# Hub.net
KiCad netlist of a schematic drawn in EAGLE
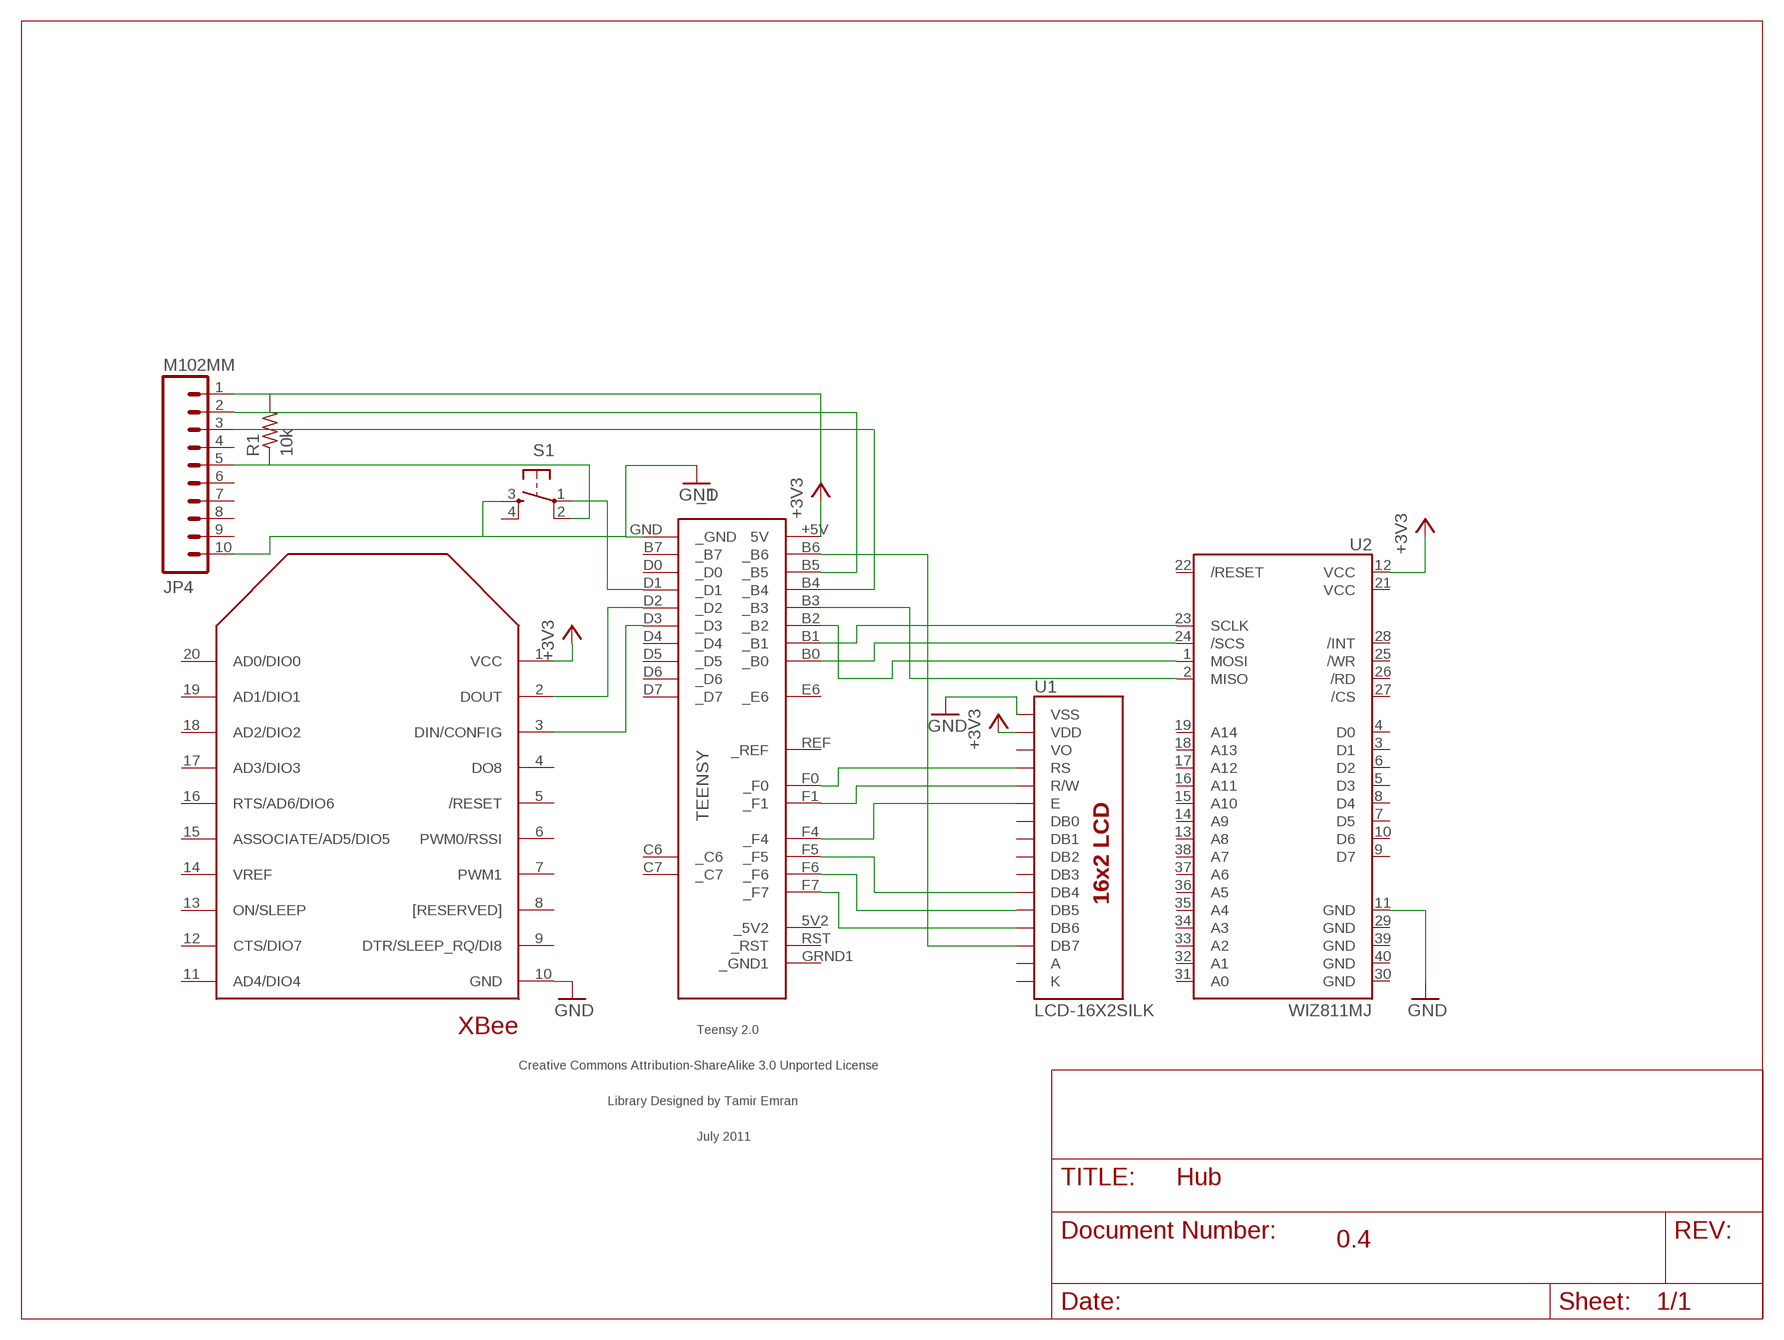
[diagram p0: schematic, sheet 1]

(export (version "E")
  (design (tool "Eeschema 10.0.6"))
  (components
    (comp (ref "JP4")
      (value "M102MM")
      (footprint "eagle-import:1X10-2MM")
      (libsource (lib "eagle-import") (part "M102MM"))
    )
    (comp (ref "R1")
      (value "10k")
      (footprint "eagle-import:0207_7")
      (libsource (lib "eagle-import") (part "R-US_0207/7"))
    )
    (comp (ref "S1")
      (value "TAC_SWITCHPTH")
      (footprint "eagle-import:TACTILE-PTH")
      (libsource (lib "eagle-import") (part "TAC_SWITCHPTH"))
    )
    (comp (ref "U$1")
      (value "XBEE")
      (footprint "eagle-import:XBEE")
      (libsource (lib "eagle-import") (part "XBEE"))
    )
    (comp (ref "U1")
      (value "LCD-16X2SILK")
      (footprint "eagle-import:LCD-16X2")
      (libsource (lib "eagle-import") (part "LCD-16X2SILK"))
    )
    (comp (ref "U2")
      (value "WIZ811MJ")
      (footprint "eagle-import:WIZ811MJ")
      (libsource (lib "eagle-import") (part "WIZ811MJ"))
    )
    (comp (ref "_1")
      (value "TEENSY")
      (footprint "eagle-import:TEENSY")
      (libsource (lib "eagle-import") (part "TEENSY"))
    )
  )
  (nets
    (net (code "1") (name "+3V3") (class "Default")
      (node (ref "U$1") (pin "1") (pinfunction "VCC_1") (pintype "bidirectional"))
      (node (ref "U1") (pin "2") (pinfunction "VDD_2") (pintype "power_in"))
      (node (ref "U2") (pin "12") (pinfunction "VCC_12") (pintype "bidirectional"))
      (node (ref "_1") (pin "+5V") (pinfunction "5V_+5V") (pintype "bidirectional"))
    )
    (net (code "2") (name "/A") (class "Default")
      (node (ref "U1") (pin "15") (pinfunction "A_15") (pintype "power_in"))
    )
    (net (code "3") (name "/K") (class "Default")
      (node (ref "U1") (pin "16") (pinfunction "K_16") (pintype "power_in"))
    )
    (net (code "4") (name "GND") (class "Default")
      (node (ref "JP4") (pin "10") (pinfunction "10_10") (pintype "passive"))
      (node (ref "S1") (pin "3") (pinfunction "3_3") (pintype "passive"))
      (node (ref "U$1") (pin "10") (pinfunction "GND_10") (pintype "bidirectional"))
      (node (ref "U1") (pin "1") (pinfunction "VSS_1") (pintype "power_in"))
      (node (ref "U2") (pin "11") (pinfunction "GND_11") (pintype "bidirectional"))
      (node (ref "_1") (pin "GND") (pinfunction "_GND_GND") (pintype "bidirectional"))
    )
    (net (code "5") (name "Net-(JP4-Pad1)") (class "Default")
      (node (ref "JP4") (pin "1") (pinfunction "1_1") (pintype "passive"))
      (node (ref "R1") (pin "2") (pinfunction "2_2") (pintype "passive"))
    )
    (net (code "6") (name "Net-(JP4-Pad5)") (class "Default")
      (node (ref "JP4") (pin "5") (pinfunction "5_5") (pintype "passive"))
      (node (ref "R1") (pin "1") (pinfunction "1_1") (pintype "passive"))
      (node (ref "S1") (pin "2") (pinfunction "2_2") (pintype "passive"))
    )
    (net (code "7") (name "Net-(U$1-DIN{slash}CONFIG)") (class "Default")
      (node (ref "U$1") (pin "3") (pinfunction "DIN/CONFIG_3") (pintype "bidirectional"))
      (node (ref "_1") (pin "D3") (pinfunction "_D3_D3") (pintype "bidirectional"))
    )
    (net (code "8") (name "Net-(U$1-DOUT)") (class "Default")
      (node (ref "U$1") (pin "2") (pinfunction "DOUT_2") (pintype "bidirectional"))
      (node (ref "_1") (pin "D2") (pinfunction "_D2_D2") (pintype "bidirectional"))
    )
    (net (code "9") (name "Net-(U1-DB4)") (class "Default")
      (node (ref "U1") (pin "11") (pinfunction "DB4_11") (pintype "bidirectional"))
      (node (ref "_1") (pin "F5") (pinfunction "_F5_F5") (pintype "bidirectional"))
    )
    (net (code "10") (name "Net-(U1-DB5)") (class "Default")
      (node (ref "U1") (pin "12") (pinfunction "DB5_12") (pintype "bidirectional"))
      (node (ref "_1") (pin "F6") (pinfunction "_F6_F6") (pintype "bidirectional"))
    )
    (net (code "11") (name "Net-(U1-DB6)") (class "Default")
      (node (ref "U1") (pin "13") (pinfunction "DB6_13") (pintype "bidirectional"))
      (node (ref "_1") (pin "F7") (pinfunction "_F7_F7") (pintype "bidirectional"))
    )
    (net (code "12") (name "Net-(U1-DB7)") (class "Default")
      (node (ref "U1") (pin "14") (pinfunction "DB7_14") (pintype "bidirectional"))
      (node (ref "_1") (pin "B6") (pinfunction "_B6_B6") (pintype "bidirectional"))
    )
    (net (code "13") (name "Net-(U1-E)") (class "Default")
      (node (ref "U1") (pin "6") (pinfunction "E_6") (pintype "input"))
      (node (ref "_1") (pin "F4") (pinfunction "_F4_F4") (pintype "bidirectional"))
    )
    (net (code "14") (name "Net-(U1-RS)") (class "Default")
      (node (ref "U1") (pin "4") (pinfunction "RS_4") (pintype "input"))
      (node (ref "_1") (pin "F0") (pinfunction "_F0_F0") (pintype "bidirectional"))
    )
    (net (code "15") (name "Net-(U1-R{slash}W)") (class "Default")
      (node (ref "U1") (pin "5") (pinfunction "R/W_5") (pintype "input"))
      (node (ref "_1") (pin "F1") (pinfunction "_F1_F1") (pintype "bidirectional"))
    )
    (net (code "16") (name "Net-(U2-MISO)") (class "Default")
      (node (ref "U2") (pin "2") (pinfunction "MISO_2") (pintype "bidirectional"))
      (node (ref "_1") (pin "B3") (pinfunction "_B3_B3") (pintype "bidirectional"))
    )
    (net (code "17") (name "Net-(U2-MOSI)") (class "Default")
      (node (ref "U2") (pin "1") (pinfunction "MOSI_1") (pintype "bidirectional"))
      (node (ref "_1") (pin "B2") (pinfunction "_B2_B2") (pintype "bidirectional"))
    )
    (net (code "18") (name "Net-(U2-SCLK)") (class "Default")
      (node (ref "U2") (pin "23") (pinfunction "SCLK_23") (pintype "bidirectional"))
      (node (ref "_1") (pin "B1") (pinfunction "_B1_B1") (pintype "bidirectional"))
    )
    (net (code "19") (name "Net-(U2-{slash}SCS)") (class "Default")
      (node (ref "U2") (pin "24") (pinfunction "/SCS_24") (pintype "bidirectional"))
      (node (ref "_1") (pin "B0") (pinfunction "_B0_B0") (pintype "bidirectional"))
    )
    (net (code "20") (name "Net-(_1-_B4)") (class "Default")
      (node (ref "JP4") (pin "3") (pinfunction "3_3") (pintype "passive"))
      (node (ref "_1") (pin "B4") (pinfunction "_B4_B4") (pintype "bidirectional"))
    )
    (net (code "21") (name "Net-(_1-_B5)") (class "Default")
      (node (ref "JP4") (pin "2") (pinfunction "2_2") (pintype "passive"))
      (node (ref "_1") (pin "B5") (pinfunction "_B5_B5") (pintype "bidirectional"))
    )
    (net (code "22") (name "Net-(_1-_D1)") (class "Default")
      (node (ref "S1") (pin "1") (pinfunction "1_1") (pintype "passive"))
      (node (ref "_1") (pin "D1") (pinfunction "_D1_D1") (pintype "bidirectional"))
    )
    (net (code "23") (name "unconnected-(JP4-Pad4)") (class "Default")
      (node (ref "JP4") (pin "4") (pinfunction "4_4") (pintype "passive"))
    )
    (net (code "24") (name "unconnected-(JP4-Pad6)") (class "Default")
      (node (ref "JP4") (pin "6") (pinfunction "6_6") (pintype "passive"))
    )
    (net (code "25") (name "unconnected-(JP4-Pad7)") (class "Default")
      (node (ref "JP4") (pin "7") (pinfunction "7_7") (pintype "passive"))
    )
    (net (code "26") (name "unconnected-(JP4-Pad8)") (class "Default")
      (node (ref "JP4") (pin "8") (pinfunction "8_8") (pintype "passive"))
    )
    (net (code "27") (name "unconnected-(JP4-Pad9)") (class "Default")
      (node (ref "JP4") (pin "9") (pinfunction "9_9") (pintype "passive"))
    )
    (net (code "28") (name "unconnected-(S1-Pad4)") (class "Default")
      (node (ref "S1") (pin "4") (pinfunction "4_4") (pintype "passive"))
    )
    (net (code "29") (name "unconnected-(U$1-AD0{slash}DIO0-Pad20)") (class "Default")
      (node (ref "U$1") (pin "20") (pinfunction "AD0/DIO0_20") (pintype "bidirectional"))
    )
    (net (code "30") (name "unconnected-(U$1-AD1{slash}DIO1-Pad19)") (class "Default")
      (node (ref "U$1") (pin "19") (pinfunction "AD1/DIO1_19") (pintype "bidirectional"))
    )
    (net (code "31") (name "unconnected-(U$1-AD2{slash}DIO2-Pad18)") (class "Default")
      (node (ref "U$1") (pin "18") (pinfunction "AD2/DIO2_18") (pintype "bidirectional"))
    )
    (net (code "32") (name "unconnected-(U$1-AD3{slash}DIO3-Pad17)") (class "Default")
      (node (ref "U$1") (pin "17") (pinfunction "AD3/DIO3_17") (pintype "bidirectional"))
    )
    (net (code "33") (name "unconnected-(U$1-AD4{slash}DIO4-Pad11)") (class "Default")
      (node (ref "U$1") (pin "11") (pinfunction "AD4/DIO4_11") (pintype "bidirectional"))
    )
    (net (code "34") (name "unconnected-(U$1-ASSOCIATE{slash}AD5{slash}DIO5-Pad15)") (class "Default")
      (node (ref "U$1") (pin "15") (pinfunction "ASSOCIATE/AD5/DIO5_15") (pintype "bidirectional"))
    )
    (net (code "35") (name "unconnected-(U$1-CTS{slash}DIO7-Pad12)") (class "Default")
      (node (ref "U$1") (pin "12") (pinfunction "CTS/DIO7_12") (pintype "bidirectional"))
    )
    (net (code "36") (name "unconnected-(U$1-DO8-Pad4)") (class "Default")
      (node (ref "U$1") (pin "4") (pinfunction "DO8_4") (pintype "bidirectional"))
    )
    (net (code "37") (name "unconnected-(U$1-DTR{slash}SLEEP_RQ{slash}DI8-Pad9)") (class "Default")
      (node (ref "U$1") (pin "9") (pinfunction "DTR/SLEEP_RQ/DI8_9") (pintype "bidirectional"))
    )
    (net (code "38") (name "unconnected-(U$1-ON{slash}SLEEP-Pad13)") (class "Default")
      (node (ref "U$1") (pin "13") (pinfunction "ON/SLEEP_13") (pintype "bidirectional"))
    )
    (net (code "39") (name "unconnected-(U$1-PWM0{slash}RSSI-Pad6)") (class "Default")
      (node (ref "U$1") (pin "6") (pinfunction "PWM0/RSSI_6") (pintype "bidirectional"))
    )
    (net (code "40") (name "unconnected-(U$1-PWM1-Pad7)") (class "Default")
      (node (ref "U$1") (pin "7") (pinfunction "PWM1_7") (pintype "bidirectional"))
    )
    (net (code "41") (name "unconnected-(U$1-RTS{slash}AD6{slash}DIO6-Pad16)") (class "Default")
      (node (ref "U$1") (pin "16") (pinfunction "RTS/AD6/DIO6_16") (pintype "bidirectional"))
    )
    (net (code "42") (name "unconnected-(U$1-VREF-Pad14)") (class "Default")
      (node (ref "U$1") (pin "14") (pinfunction "VREF_14") (pintype "bidirectional"))
    )
    (net (code "43") (name "unconnected-(U$1-[RESERVED]-Pad8)") (class "Default")
      (node (ref "U$1") (pin "8") (pinfunction "[RESERVED]_8") (pintype "bidirectional"))
    )
    (net (code "44") (name "unconnected-(U$1-{slash}RESET-Pad5)") (class "Default")
      (node (ref "U$1") (pin "5") (pinfunction "/RESET_5") (pintype "bidirectional"))
    )
    (net (code "45") (name "unconnected-(U1-DB0-Pad7)") (class "Default")
      (node (ref "U1") (pin "7") (pinfunction "DB0_7") (pintype "bidirectional"))
    )
    (net (code "46") (name "unconnected-(U1-DB1-Pad8)") (class "Default")
      (node (ref "U1") (pin "8") (pinfunction "DB1_8") (pintype "bidirectional"))
    )
    (net (code "47") (name "unconnected-(U1-DB2-Pad9)") (class "Default")
      (node (ref "U1") (pin "9") (pinfunction "DB2_9") (pintype "bidirectional"))
    )
    (net (code "48") (name "unconnected-(U1-DB3-Pad10)") (class "Default")
      (node (ref "U1") (pin "10") (pinfunction "DB3_10") (pintype "bidirectional"))
    )
    (net (code "49") (name "unconnected-(U1-VO-Pad3)") (class "Default")
      (node (ref "U1") (pin "3") (pinfunction "VO_3") (pintype "bidirectional"))
    )
    (net (code "50") (name "unconnected-(U2-A0-Pad31)") (class "Default")
      (node (ref "U2") (pin "31") (pinfunction "A0_31") (pintype "bidirectional"))
    )
    (net (code "51") (name "unconnected-(U2-A1-Pad32)") (class "Default")
      (node (ref "U2") (pin "32") (pinfunction "A1_32") (pintype "bidirectional"))
    )
    (net (code "52") (name "unconnected-(U2-A2-Pad33)") (class "Default")
      (node (ref "U2") (pin "33") (pinfunction "A2_33") (pintype "bidirectional"))
    )
    (net (code "53") (name "unconnected-(U2-A3-Pad34)") (class "Default")
      (node (ref "U2") (pin "34") (pinfunction "A3_34") (pintype "bidirectional"))
    )
    (net (code "54") (name "unconnected-(U2-A4-Pad35)") (class "Default")
      (node (ref "U2") (pin "35") (pinfunction "A4_35") (pintype "bidirectional"))
    )
    (net (code "55") (name "unconnected-(U2-A5-Pad36)") (class "Default")
      (node (ref "U2") (pin "36") (pinfunction "A5_36") (pintype "bidirectional"))
    )
    (net (code "56") (name "unconnected-(U2-A6-Pad37)") (class "Default")
      (node (ref "U2") (pin "37") (pinfunction "A6_37") (pintype "bidirectional"))
    )
    (net (code "57") (name "unconnected-(U2-A7-Pad38)") (class "Default")
      (node (ref "U2") (pin "38") (pinfunction "A7_38") (pintype "bidirectional"))
    )
    (net (code "58") (name "unconnected-(U2-A8-Pad13)") (class "Default")
      (node (ref "U2") (pin "13") (pinfunction "A8_13") (pintype "bidirectional"))
    )
    (net (code "59") (name "unconnected-(U2-A9-Pad14)") (class "Default")
      (node (ref "U2") (pin "14") (pinfunction "A9_14") (pintype "bidirectional"))
    )
    (net (code "60") (name "unconnected-(U2-A10-Pad15)") (class "Default")
      (node (ref "U2") (pin "15") (pinfunction "A10_15") (pintype "bidirectional"))
    )
    (net (code "61") (name "unconnected-(U2-A11-Pad16)") (class "Default")
      (node (ref "U2") (pin "16") (pinfunction "A11_16") (pintype "bidirectional"))
    )
    (net (code "62") (name "unconnected-(U2-A12-Pad17)") (class "Default")
      (node (ref "U2") (pin "17") (pinfunction "A12_17") (pintype "bidirectional"))
    )
    (net (code "63") (name "unconnected-(U2-A13-Pad18)") (class "Default")
      (node (ref "U2") (pin "18") (pinfunction "A13_18") (pintype "bidirectional"))
    )
    (net (code "64") (name "unconnected-(U2-A14-Pad19)") (class "Default")
      (node (ref "U2") (pin "19") (pinfunction "A14_19") (pintype "bidirectional"))
    )
    (net (code "65") (name "unconnected-(U2-D0-Pad4)") (class "Default")
      (node (ref "U2") (pin "4") (pinfunction "D0_4") (pintype "bidirectional"))
    )
    (net (code "66") (name "unconnected-(U2-D1-Pad3)") (class "Default")
      (node (ref "U2") (pin "3") (pinfunction "D1_3") (pintype "bidirectional"))
    )
    (net (code "67") (name "unconnected-(U2-D2-Pad6)") (class "Default")
      (node (ref "U2") (pin "6") (pinfunction "D2_6") (pintype "bidirectional"))
    )
    (net (code "68") (name "unconnected-(U2-D3-Pad5)") (class "Default")
      (node (ref "U2") (pin "5") (pinfunction "D3_5") (pintype "bidirectional"))
    )
    (net (code "69") (name "unconnected-(U2-D4-Pad8)") (class "Default")
      (node (ref "U2") (pin "8") (pinfunction "D4_8") (pintype "bidirectional"))
    )
    (net (code "70") (name "unconnected-(U2-D5-Pad7)") (class "Default")
      (node (ref "U2") (pin "7") (pinfunction "D5_7") (pintype "bidirectional"))
    )
    (net (code "71") (name "unconnected-(U2-D6-Pad10)") (class "Default")
      (node (ref "U2") (pin "10") (pinfunction "D6_10") (pintype "bidirectional"))
    )
    (net (code "72") (name "unconnected-(U2-D7-Pad9)") (class "Default")
      (node (ref "U2") (pin "9") (pinfunction "D7_9") (pintype "bidirectional"))
    )
    (net (code "73") (name "unconnected-(U2-GND-Pad29)") (class "Default")
      (node (ref "U2") (pin "29") (pinfunction "GND_29") (pintype "bidirectional"))
    )
    (net (code "74") (name "unconnected-(U2-GND-Pad30)") (class "Default")
      (node (ref "U2") (pin "30") (pinfunction "GND_30") (pintype "bidirectional"))
    )
    (net (code "75") (name "unconnected-(U2-GND-Pad39)") (class "Default")
      (node (ref "U2") (pin "39") (pinfunction "GND_39") (pintype "bidirectional"))
    )
    (net (code "76") (name "unconnected-(U2-GND-Pad40)") (class "Default")
      (node (ref "U2") (pin "40") (pinfunction "GND_40") (pintype "bidirectional"))
    )
    (net (code "77") (name "unconnected-(U2-VCC-Pad21)") (class "Default")
      (node (ref "U2") (pin "21") (pinfunction "VCC_21") (pintype "bidirectional"))
    )
    (net (code "78") (name "unconnected-(U2-{slash}CS-Pad27)") (class "Default")
      (node (ref "U2") (pin "27") (pinfunction "/CS_27") (pintype "bidirectional"))
    )
    (net (code "79") (name "unconnected-(U2-{slash}INT-Pad28)") (class "Default")
      (node (ref "U2") (pin "28") (pinfunction "/INT_28") (pintype "bidirectional"))
    )
    (net (code "80") (name "unconnected-(U2-{slash}RD-Pad26)") (class "Default")
      (node (ref "U2") (pin "26") (pinfunction "/RD_26") (pintype "bidirectional"))
    )
    (net (code "81") (name "unconnected-(U2-{slash}RESET-Pad22)") (class "Default")
      (node (ref "U2") (pin "22") (pinfunction "/RESET_22") (pintype "bidirectional"))
    )
    (net (code "82") (name "unconnected-(U2-{slash}WR-Pad25)") (class "Default")
      (node (ref "U2") (pin "25") (pinfunction "/WR_25") (pintype "bidirectional"))
    )
    (net (code "83") (name "unconnected-(_1-_5V2-Pad5V2)") (class "Default")
      (node (ref "_1") (pin "5V2") (pinfunction "_5V2_5V2") (pintype "bidirectional"))
    )
    (net (code "84") (name "unconnected-(_1-_B7-PadB7)") (class "Default")
      (node (ref "_1") (pin "B7") (pinfunction "_B7_B7") (pintype "bidirectional"))
    )
    (net (code "85") (name "unconnected-(_1-_C6-PadC6)") (class "Default")
      (node (ref "_1") (pin "C6") (pinfunction "_C6_C6") (pintype "bidirectional"))
    )
    (net (code "86") (name "unconnected-(_1-_C7-PadC7)") (class "Default")
      (node (ref "_1") (pin "C7") (pinfunction "_C7_C7") (pintype "bidirectional"))
    )
    (net (code "87") (name "unconnected-(_1-_D0-PadD0)") (class "Default")
      (node (ref "_1") (pin "D0") (pinfunction "_D0_D0") (pintype "bidirectional"))
    )
    (net (code "88") (name "unconnected-(_1-_D4-PadD4)") (class "Default")
      (node (ref "_1") (pin "D4") (pinfunction "_D4_D4") (pintype "bidirectional"))
    )
    (net (code "89") (name "unconnected-(_1-_D5-PadD5)") (class "Default")
      (node (ref "_1") (pin "D5") (pinfunction "_D5_D5") (pintype "bidirectional"))
    )
    (net (code "90") (name "unconnected-(_1-_D6-PadD6)") (class "Default")
      (node (ref "_1") (pin "D6") (pinfunction "_D6_D6") (pintype "bidirectional"))
    )
    (net (code "91") (name "unconnected-(_1-_D7-PadD7)") (class "Default")
      (node (ref "_1") (pin "D7") (pinfunction "_D7_D7") (pintype "bidirectional"))
    )
    (net (code "92") (name "unconnected-(_1-_E6-PadE6)") (class "Default")
      (node (ref "_1") (pin "E6") (pinfunction "_E6_E6") (pintype "bidirectional"))
    )
    (net (code "93") (name "unconnected-(_1-_GND1-PadGRND1)") (class "Default")
      (node (ref "_1") (pin "GRND1") (pinfunction "_GND1_GRND1") (pintype "bidirectional"))
    )
    (net (code "94") (name "unconnected-(_1-_REF-PadREF)") (class "Default")
      (node (ref "_1") (pin "REF") (pinfunction "_REF_REF") (pintype "bidirectional"))
    )
    (net (code "95") (name "unconnected-(_1-_RST-PadRST)") (class "Default")
      (node (ref "_1") (pin "RST") (pinfunction "_RST_RST") (pintype "bidirectional"))
    )
  )
)
